# pcb.net
KiCad netlist of a schematic drawn in EAGLE
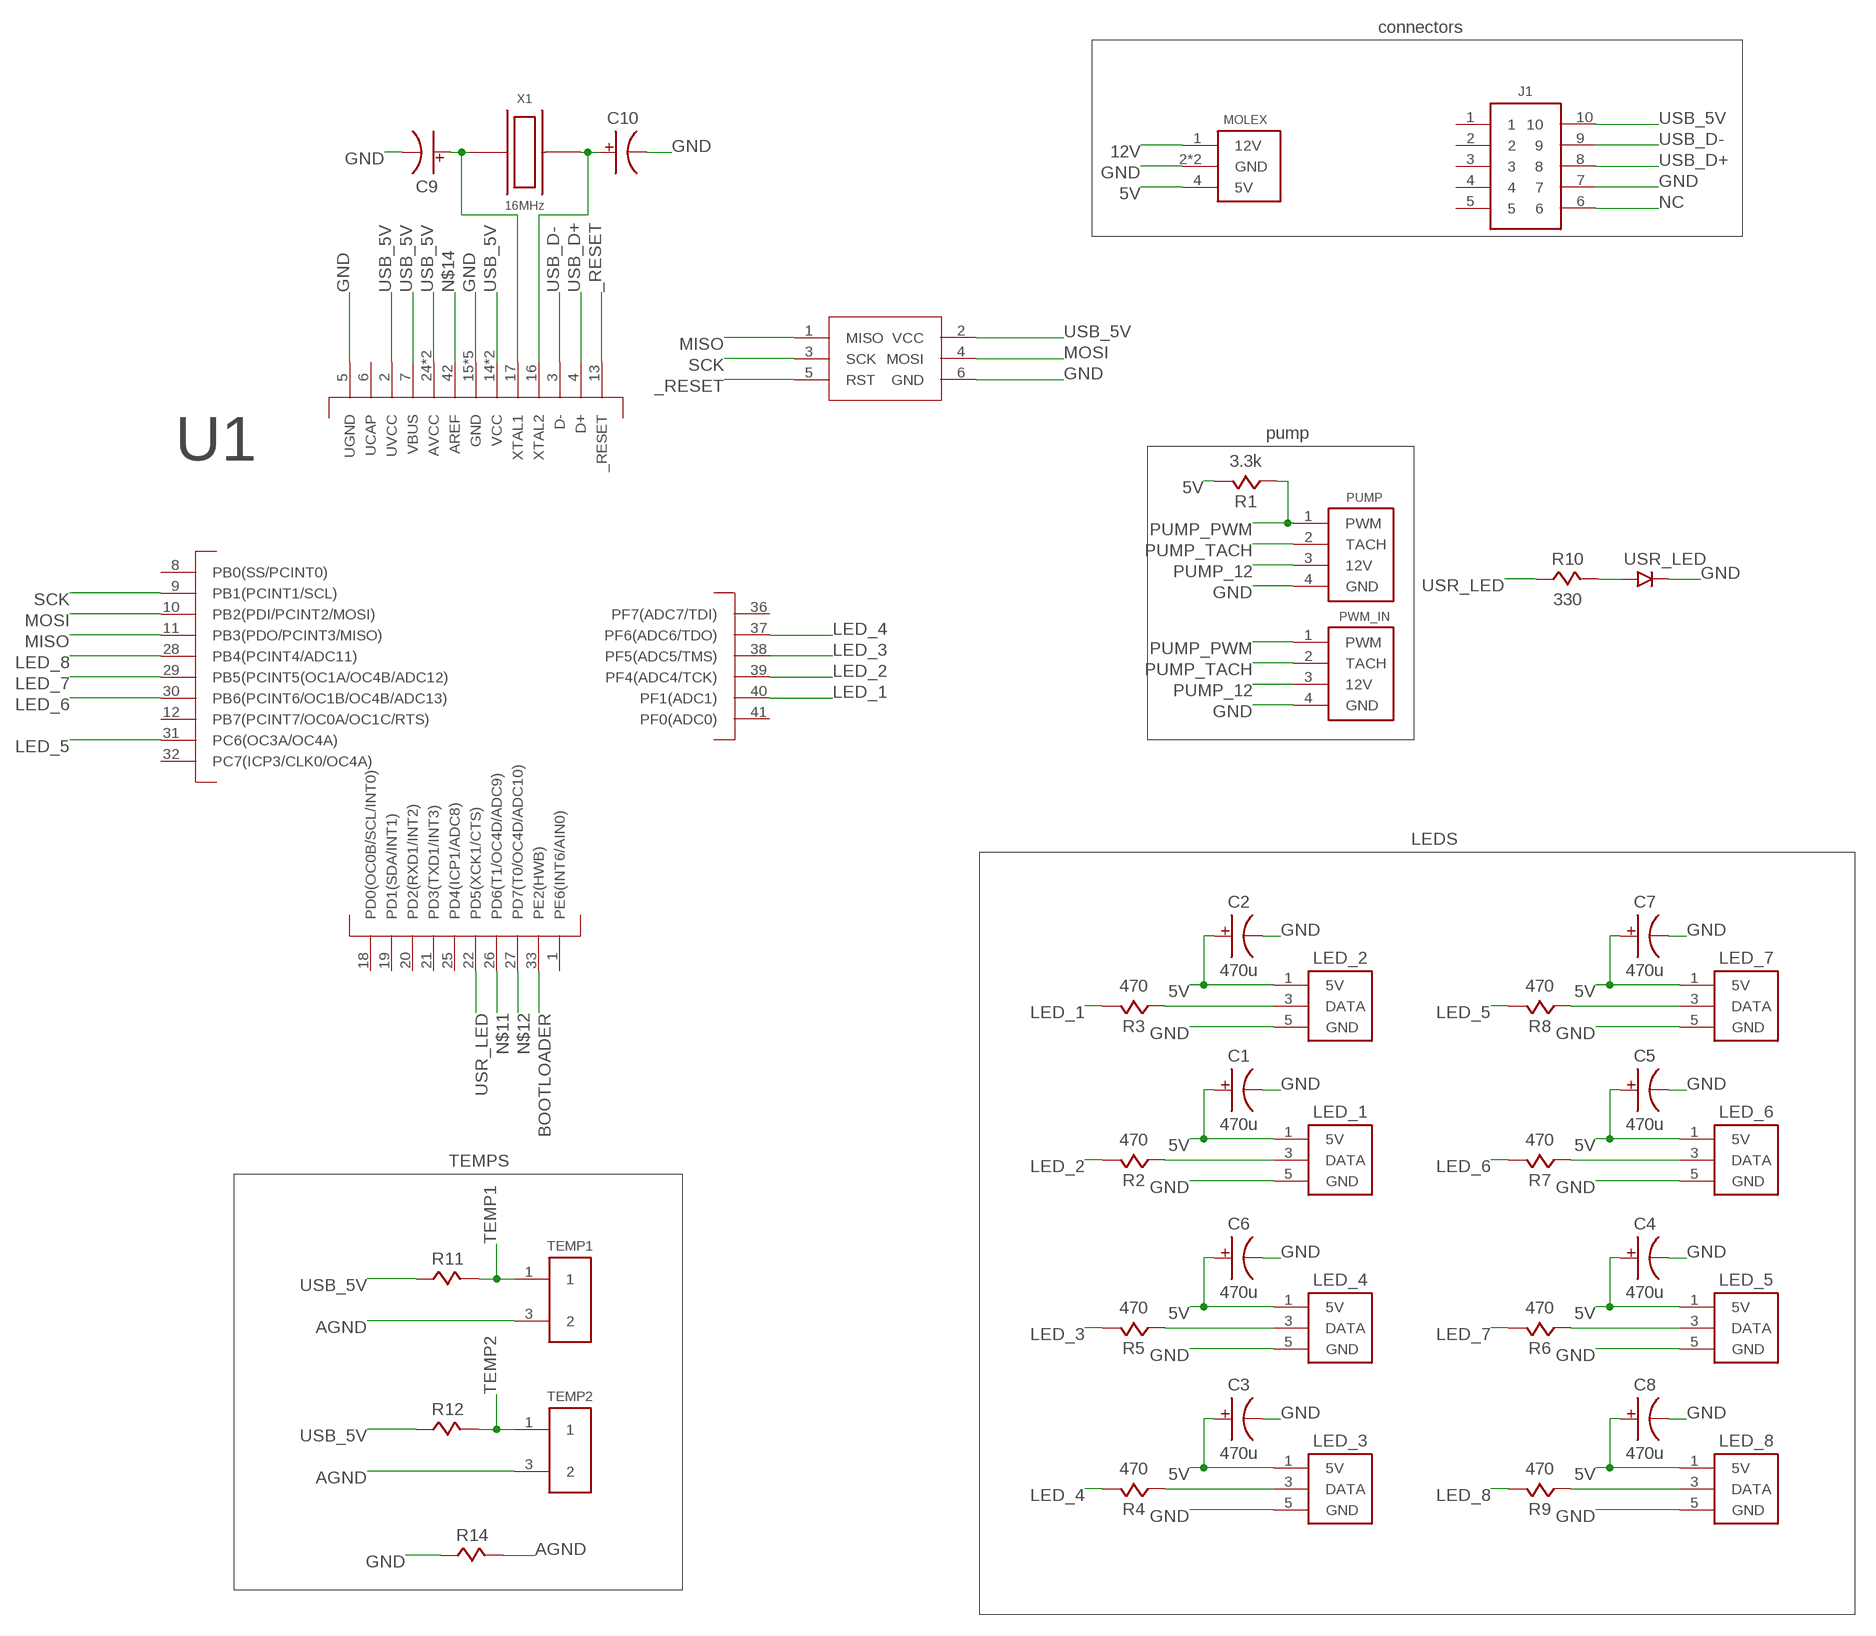
[diagram p0: schematic, sheet 1]

(export (version "E")
  (design (tool "Eeschema 10.0.6"))
  (components
    (comp (ref "C1")
      (value "470u")
      (footprint "eagle-import:0805")
      (libsource (lib "eagle-import") (part "CAPACITOR0805"))
    )
    (comp (ref "C2")
      (value "470u")
      (footprint "eagle-import:0805")
      (libsource (lib "eagle-import") (part "CAPACITOR0805"))
    )
    (comp (ref "C3")
      (value "470u")
      (footprint "eagle-import:0805")
      (libsource (lib "eagle-import") (part "CAPACITOR0805"))
    )
    (comp (ref "C4")
      (value "470u")
      (footprint "eagle-import:0805")
      (libsource (lib "eagle-import") (part "CAPACITOR0805"))
    )
    (comp (ref "C5")
      (value "470u")
      (footprint "eagle-import:0805")
      (libsource (lib "eagle-import") (part "CAPACITOR0805"))
    )
    (comp (ref "C6")
      (value "470u")
      (footprint "eagle-import:0805")
      (libsource (lib "eagle-import") (part "CAPACITOR0805"))
    )
    (comp (ref "C7")
      (value "470u")
      (footprint "eagle-import:0805")
      (libsource (lib "eagle-import") (part "CAPACITOR0805"))
    )
    (comp (ref "C8")
      (value "470u")
      (footprint "eagle-import:0805")
      (libsource (lib "eagle-import") (part "CAPACITOR0805"))
    )
    (comp (ref "C9")
      (value "CAPACITOR0805")
      (footprint "eagle-import:0805")
      (libsource (lib "eagle-import") (part "CAPACITOR0805"))
    )
    (comp (ref "C10")
      (value "CAPACITOR0805")
      (footprint "eagle-import:0805")
      (libsource (lib "eagle-import") (part "CAPACITOR0805"))
    )
    (comp (ref "J1")
      (value "FEMALE_HEADER_5X2SMT")
      (footprint "eagle-import:5X2_HEADER_SMT")
      (libsource (lib "eagle-import") (part "FEMALE_HEADER_5X2SMT"))
    )
    (comp (ref "J2")
      (value "ISP_CONN_6PIN")
      (footprint "eagle-import:3X2_HEADER_SMT")
      (libsource (lib "eagle-import") (part "ISP_CONN_6PIN"))
    )
    (comp (ref "LED_1")
      (value "WS2812B_3")
      (footprint "eagle-import:3X1_HEADER")
      (libsource (lib "eagle-import") (part "WS2812B_3"))
    )
    (comp (ref "LED_2")
      (value "WS2812B_3")
      (footprint "eagle-import:3X1_HEADER")
      (libsource (lib "eagle-import") (part "WS2812B_3"))
    )
    (comp (ref "LED_3")
      (value "WS2812B_3")
      (footprint "eagle-import:3X1_HEADER")
      (libsource (lib "eagle-import") (part "WS2812B_3"))
    )
    (comp (ref "LED_4")
      (value "WS2812B_3")
      (footprint "eagle-import:3X1_HEADER")
      (libsource (lib "eagle-import") (part "WS2812B_3"))
    )
    (comp (ref "LED_5")
      (value "WS2812B_3")
      (footprint "eagle-import:3X1_HEADER")
      (libsource (lib "eagle-import") (part "WS2812B_3"))
    )
    (comp (ref "LED_6")
      (value "WS2812B_3")
      (footprint "eagle-import:3X1_HEADER")
      (libsource (lib "eagle-import") (part "WS2812B_3"))
    )
    (comp (ref "LED_7")
      (value "WS2812B_3")
      (footprint "eagle-import:3X1_HEADER")
      (libsource (lib "eagle-import") (part "WS2812B_3"))
    )
    (comp (ref "LED_8")
      (value "WS2812B_3")
      (footprint "eagle-import:3X1_HEADER")
      (libsource (lib "eagle-import") (part "WS2812B_3"))
    )
    (comp (ref "MOLEX")
      (value "MOLEX_POWER")
      (footprint "eagle-import:MOLEX_POWER")
      (libsource (lib "eagle-import") (part "MOLEX_POWER"))
    )
    (comp (ref "PUMP")
      (value "4PIN_LED_HEADER")
      (footprint "eagle-import:4PIN_FAN_HEADER_THT")
      (libsource (lib "eagle-import") (part "4PIN_LED_HEADER"))
    )
    (comp (ref "PWM_IN")
      (value "4PIN_LED_HEADER")
      (footprint "eagle-import:4PIN_FAN_HEADER_THT")
      (libsource (lib "eagle-import") (part "4PIN_LED_HEADER"))
    )
    (comp (ref "R1")
      (value "3.3k")
      (footprint "eagle-import:0805")
      (libsource (lib "eagle-import") (part "RESISTOR"))
    )
    (comp (ref "R2")
      (value "470")
      (footprint "eagle-import:0805")
      (libsource (lib "eagle-import") (part "RESISTOR"))
    )
    (comp (ref "R3")
      (value "470")
      (footprint "eagle-import:0805")
      (libsource (lib "eagle-import") (part "RESISTOR"))
    )
    (comp (ref "R4")
      (value "470")
      (footprint "eagle-import:0805")
      (libsource (lib "eagle-import") (part "RESISTOR"))
    )
    (comp (ref "R5")
      (value "470")
      (footprint "eagle-import:0805")
      (libsource (lib "eagle-import") (part "RESISTOR"))
    )
    (comp (ref "R6")
      (value "470")
      (footprint "eagle-import:0805")
      (libsource (lib "eagle-import") (part "RESISTOR"))
    )
    (comp (ref "R7")
      (value "470")
      (footprint "eagle-import:0805")
      (libsource (lib "eagle-import") (part "RESISTOR"))
    )
    (comp (ref "R8")
      (value "470")
      (footprint "eagle-import:0805")
      (libsource (lib "eagle-import") (part "RESISTOR"))
    )
    (comp (ref "R9")
      (value "470")
      (footprint "eagle-import:0805")
      (libsource (lib "eagle-import") (part "RESISTOR"))
    )
    (comp (ref "R10")
      (value "330")
      (footprint "eagle-import:0805")
      (libsource (lib "eagle-import") (part "RESISTOR"))
    )
    (comp (ref "R11")
      (value "RESISTOR")
      (footprint "eagle-import:0805")
      (libsource (lib "eagle-import") (part "RESISTOR"))
    )
    (comp (ref "R12")
      (value "RESISTOR")
      (footprint "eagle-import:0805")
      (libsource (lib "eagle-import") (part "RESISTOR"))
    )
    (comp (ref "R14")
      (value "RESISTOR")
      (footprint "eagle-import:0805")
      (libsource (lib "eagle-import") (part "RESISTOR"))
    )
    (comp (ref "TEMP1")
      (value "FEMALE_HEADER_2X1")
      (footprint "eagle-import:2X1_HEADER")
      (libsource (lib "eagle-import") (part "FEMALE_HEADER_2X1"))
    )
    (comp (ref "TEMP2")
      (value "FEMALE_HEADER_2X1")
      (footprint "eagle-import:2X1_HEADER")
      (libsource (lib "eagle-import") (part "FEMALE_HEADER_2X1"))
    )
    (comp (ref "U1")
      (value "ATMEGA32U4")
      (footprint "eagle-import:QFN44")
      (libsource (lib "eagle-import") (part "ATMEGA32U4"))
    )
    (comp (ref "USR_LED")
      (value "LED")
      (footprint "eagle-import:0805")
      (libsource (lib "eagle-import") (part "LED"))
    )
    (comp (ref "X1")
      (value "16MHz")
      (footprint "eagle-import:3.2X2.5_OSC")
      (libsource (lib "eagle-import") (part "QUARTZ"))
    )
  )
  (nets
    (net (code "1") (name "/5V") (class "Default")
      (node (ref "C1") (pin "1") (pinfunction "P$1_1") (pintype "bidirectional"))
      (node (ref "C2") (pin "1") (pinfunction "P$1_1") (pintype "bidirectional"))
      (node (ref "C3") (pin "1") (pinfunction "P$1_1") (pintype "bidirectional"))
      (node (ref "C4") (pin "1") (pinfunction "P$1_1") (pintype "bidirectional"))
      (node (ref "C5") (pin "1") (pinfunction "P$1_1") (pintype "bidirectional"))
      (node (ref "C6") (pin "1") (pinfunction "P$1_1") (pintype "bidirectional"))
      (node (ref "C7") (pin "1") (pinfunction "P$1_1") (pintype "bidirectional"))
      (node (ref "C8") (pin "1") (pinfunction "P$1_1") (pintype "bidirectional"))
      (node (ref "LED_1") (pin "1") (pinfunction "5V_1") (pintype "bidirectional"))
      (node (ref "LED_2") (pin "1") (pinfunction "5V_1") (pintype "bidirectional"))
      (node (ref "LED_3") (pin "1") (pinfunction "5V_1") (pintype "bidirectional"))
      (node (ref "LED_4") (pin "1") (pinfunction "5V_1") (pintype "bidirectional"))
      (node (ref "LED_5") (pin "1") (pinfunction "5V_1") (pintype "bidirectional"))
      (node (ref "LED_6") (pin "1") (pinfunction "5V_1") (pintype "bidirectional"))
      (node (ref "LED_7") (pin "1") (pinfunction "5V_1") (pintype "bidirectional"))
      (node (ref "LED_8") (pin "1") (pinfunction "5V_1") (pintype "bidirectional"))
      (node (ref "MOLEX") (pin "4") (pinfunction "5V_4") (pintype "bidirectional"))
      (node (ref "R1") (pin "2") (pinfunction "2_2") (pintype "bidirectional"))
    )
    (net (code "2") (name "/12V") (class "Default")
      (node (ref "MOLEX") (pin "1") (pinfunction "12V_1") (pintype "bidirectional"))
    )
    (net (code "3") (name "/AGND") (class "Default")
      (node (ref "R14") (pin "2") (pinfunction "2_2") (pintype "bidirectional"))
      (node (ref "TEMP1") (pin "3") (pinfunction "2_3") (pintype "bidirectional"))
      (node (ref "TEMP2") (pin "3") (pinfunction "2_3") (pintype "bidirectional"))
    )
    (net (code "4") (name "/BOOTLOADER") (class "Default")
      (node (ref "U1") (pin "33") (pinfunction "PE2(HWB)_33") (pintype "bidirectional"))
    )
    (net (code "5") (name "/GND") (class "Default")
      (node (ref "C1") (pin "2") (pinfunction "P$2_2") (pintype "bidirectional"))
      (node (ref "C10") (pin "2") (pinfunction "P$2_2") (pintype "bidirectional"))
      (node (ref "C2") (pin "2") (pinfunction "P$2_2") (pintype "bidirectional"))
      (node (ref "C3") (pin "2") (pinfunction "P$2_2") (pintype "bidirectional"))
      (node (ref "C4") (pin "2") (pinfunction "P$2_2") (pintype "bidirectional"))
      (node (ref "C5") (pin "2") (pinfunction "P$2_2") (pintype "bidirectional"))
      (node (ref "C6") (pin "2") (pinfunction "P$2_2") (pintype "bidirectional"))
      (node (ref "C7") (pin "2") (pinfunction "P$2_2") (pintype "bidirectional"))
      (node (ref "C8") (pin "2") (pinfunction "P$2_2") (pintype "bidirectional"))
      (node (ref "C9") (pin "2") (pinfunction "P$2_2") (pintype "bidirectional"))
      (node (ref "J1") (pin "7") (pinfunction "7_7") (pintype "bidirectional"))
      (node (ref "J2") (pin "6") (pinfunction "GND_6") (pintype "bidirectional"))
      (node (ref "LED_1") (pin "5") (pinfunction "GND_5") (pintype "bidirectional"))
      (node (ref "LED_2") (pin "5") (pinfunction "GND_5") (pintype "bidirectional"))
      (node (ref "LED_3") (pin "5") (pinfunction "GND_5") (pintype "bidirectional"))
      (node (ref "LED_4") (pin "5") (pinfunction "GND_5") (pintype "bidirectional"))
      (node (ref "LED_5") (pin "5") (pinfunction "GND_5") (pintype "bidirectional"))
      (node (ref "LED_6") (pin "5") (pinfunction "GND_5") (pintype "bidirectional"))
      (node (ref "LED_7") (pin "5") (pinfunction "GND_5") (pintype "bidirectional"))
      (node (ref "LED_8") (pin "5") (pinfunction "GND_5") (pintype "bidirectional"))
      (node (ref "MOLEX") (pin "2") (pinfunction "GND_2") (pintype "bidirectional"))
      (node (ref "MOLEX") (pin "3") (pinfunction "GND_3") (pintype "bidirectional"))
      (node (ref "PUMP") (pin "4") (pinfunction "GND_4") (pintype "bidirectional"))
      (node (ref "PWM_IN") (pin "4") (pinfunction "GND_4") (pintype "bidirectional"))
      (node (ref "R14") (pin "1") (pinfunction "1_1") (pintype "bidirectional"))
      (node (ref "U1") (pin "15") (pinfunction "GND_15") (pintype "bidirectional"))
      (node (ref "U1") (pin "23") (pinfunction "GND_23") (pintype "bidirectional"))
      (node (ref "U1") (pin "35") (pinfunction "GND_35") (pintype "bidirectional"))
      (node (ref "U1") (pin "43") (pinfunction "GND_43") (pintype "bidirectional"))
      (node (ref "U1") (pin "45") (pinfunction "GND_45") (pintype "bidirectional"))
      (node (ref "U1") (pin "5") (pinfunction "UGND_5") (pintype "bidirectional"))
      (node (ref "USR_LED") (pin "2") (pinfunction "2_2") (pintype "bidirectional"))
    )
    (net (code "6") (name "/LED_1") (class "Default")
      (node (ref "R3") (pin "2") (pinfunction "2_2") (pintype "bidirectional"))
      (node (ref "U1") (pin "40") (pinfunction "PF1(ADC1)_40") (pintype "bidirectional"))
    )
    (net (code "7") (name "/LED_2") (class "Default")
      (node (ref "R2") (pin "2") (pinfunction "2_2") (pintype "bidirectional"))
      (node (ref "U1") (pin "39") (pinfunction "PF4(ADC4/TCK)_39") (pintype "bidirectional"))
    )
    (net (code "8") (name "/LED_3") (class "Default")
      (node (ref "R5") (pin "2") (pinfunction "2_2") (pintype "bidirectional"))
      (node (ref "U1") (pin "38") (pinfunction "PF5(ADC5/TMS)_38") (pintype "bidirectional"))
    )
    (net (code "9") (name "/LED_4") (class "Default")
      (node (ref "R4") (pin "2") (pinfunction "2_2") (pintype "bidirectional"))
      (node (ref "U1") (pin "37") (pinfunction "PF6(ADC6/TDO)_37") (pintype "bidirectional"))
    )
    (net (code "10") (name "/LED_5") (class "Default")
      (node (ref "R8") (pin "2") (pinfunction "2_2") (pintype "bidirectional"))
      (node (ref "U1") (pin "31") (pinfunction "PC6(OC3A/OC4A)_31") (pintype "bidirectional"))
    )
    (net (code "11") (name "/LED_6") (class "Default")
      (node (ref "R7") (pin "2") (pinfunction "2_2") (pintype "bidirectional"))
      (node (ref "U1") (pin "30") (pinfunction "PB6(PCINT6/OC1B/OC4B/ADC13)_30") (pintype "bidirectional"))
    )
    (net (code "12") (name "/LED_7") (class "Default")
      (node (ref "R6") (pin "2") (pinfunction "2_2") (pintype "bidirectional"))
      (node (ref "U1") (pin "29") (pinfunction "PB5(PCINT5(OC1A/OC4B/ADC12)_29") (pintype "bidirectional"))
    )
    (net (code "13") (name "/LED_8") (class "Default")
      (node (ref "R9") (pin "2") (pinfunction "2_2") (pintype "bidirectional"))
      (node (ref "U1") (pin "28") (pinfunction "PB4(PCINT4/ADC11)_28") (pintype "bidirectional"))
    )
    (net (code "14") (name "/MISO") (class "Default")
      (node (ref "J2") (pin "1") (pinfunction "MISO_1") (pintype "bidirectional"))
      (node (ref "U1") (pin "11") (pinfunction "PB3(PDO/PCINT3/MISO)_11") (pintype "bidirectional"))
    )
    (net (code "15") (name "/MOSI") (class "Default")
      (node (ref "J2") (pin "4") (pinfunction "MOSI_4") (pintype "bidirectional"))
      (node (ref "U1") (pin "10") (pinfunction "PB2(PDI/PCINT2/MOSI)_10") (pintype "bidirectional"))
    )
    (net (code "16") (name "/N$11") (class "Default")
      (node (ref "U1") (pin "26") (pinfunction "PD6(T1/OC4D/ADC9)_26") (pintype "bidirectional"))
    )
    (net (code "17") (name "/N$12") (class "Default")
      (node (ref "U1") (pin "27") (pinfunction "PD7(T0/OC4D/ADC10)_27") (pintype "bidirectional"))
    )
    (net (code "18") (name "/N$14") (class "Default")
      (node (ref "U1") (pin "42") (pinfunction "AREF_42") (pintype "bidirectional"))
    )
    (net (code "19") (name "/NC") (class "Default")
      (node (ref "J1") (pin "6") (pinfunction "6_6") (pintype "bidirectional"))
    )
    (net (code "20") (name "/PUMP_12") (class "Default")
      (node (ref "PUMP") (pin "3") (pinfunction "12V_3") (pintype "bidirectional"))
      (node (ref "PWM_IN") (pin "3") (pinfunction "12V_3") (pintype "bidirectional"))
    )
    (net (code "21") (name "/PUMP_PWM") (class "Default")
      (node (ref "PUMP") (pin "1") (pinfunction "PWM_1") (pintype "bidirectional"))
      (node (ref "PWM_IN") (pin "1") (pinfunction "PWM_1") (pintype "bidirectional"))
      (node (ref "R1") (pin "1") (pinfunction "1_1") (pintype "bidirectional"))
    )
    (net (code "22") (name "/PUMP_TACH") (class "Default")
      (node (ref "PUMP") (pin "2") (pinfunction "TACH_2") (pintype "bidirectional"))
      (node (ref "PWM_IN") (pin "2") (pinfunction "TACH_2") (pintype "bidirectional"))
    )
    (net (code "23") (name "/SCK") (class "Default")
      (node (ref "J2") (pin "3") (pinfunction "SCK_3") (pintype "bidirectional"))
      (node (ref "U1") (pin "9") (pinfunction "PB1(PCINT1/SCL)_9") (pintype "bidirectional"))
    )
    (net (code "24") (name "/TEMP1") (class "Default")
      (node (ref "R11") (pin "2") (pinfunction "2_2") (pintype "bidirectional"))
      (node (ref "TEMP1") (pin "1") (pinfunction "1_1") (pintype "bidirectional"))
    )
    (net (code "25") (name "/TEMP2") (class "Default")
      (node (ref "R12") (pin "2") (pinfunction "2_2") (pintype "bidirectional"))
      (node (ref "TEMP2") (pin "1") (pinfunction "1_1") (pintype "bidirectional"))
    )
    (net (code "26") (name "/USB_5V") (class "Default")
      (node (ref "J1") (pin "10") (pinfunction "10_10") (pintype "bidirectional"))
      (node (ref "J2") (pin "2") (pinfunction "VCC_2") (pintype "bidirectional"))
      (node (ref "R11") (pin "1") (pinfunction "1_1") (pintype "bidirectional"))
      (node (ref "R12") (pin "1") (pinfunction "1_1") (pintype "bidirectional"))
      (node (ref "U1") (pin "14") (pinfunction "VCC_14") (pintype "bidirectional"))
      (node (ref "U1") (pin "2") (pinfunction "UVCC_2") (pintype "bidirectional"))
      (node (ref "U1") (pin "24") (pinfunction "AVCC_24") (pintype "bidirectional"))
      (node (ref "U1") (pin "34") (pinfunction "VCC_34") (pintype "bidirectional"))
      (node (ref "U1") (pin "44") (pinfunction "AVCC_44") (pintype "bidirectional"))
      (node (ref "U1") (pin "7") (pinfunction "VBUS_7") (pintype "bidirectional"))
    )
    (net (code "27") (name "/USB_D+") (class "Default")
      (node (ref "J1") (pin "8") (pinfunction "8_8") (pintype "bidirectional"))
      (node (ref "U1") (pin "4") (pinfunction "D+_4") (pintype "bidirectional"))
    )
    (net (code "28") (name "/USB_D-") (class "Default")
      (node (ref "J1") (pin "9") (pinfunction "9_9") (pintype "bidirectional"))
      (node (ref "U1") (pin "3") (pinfunction "D-_3") (pintype "bidirectional"))
    )
    (net (code "29") (name "/USR_LED") (class "Default")
      (node (ref "R10") (pin "1") (pinfunction "1_1") (pintype "bidirectional"))
      (node (ref "U1") (pin "22") (pinfunction "PD5(XCK1/CTS)_22") (pintype "bidirectional"))
    )
    (net (code "30") (name "/_RESET") (class "Default")
      (node (ref "J2") (pin "5") (pinfunction "RST_5") (pintype "bidirectional"))
      (node (ref "U1") (pin "13") (pinfunction "_RESET_13") (pintype "bidirectional"))
    )
    (net (code "31") (name "Net-(C9-P$1)") (class "Default")
      (node (ref "C9") (pin "1") (pinfunction "P$1_1") (pintype "bidirectional"))
      (node (ref "U1") (pin "17") (pinfunction "XTAL1_17") (pintype "bidirectional"))
      (node (ref "X1") (pin "1") (pinfunction "P$1_1") (pintype "bidirectional"))
    )
    (net (code "32") (name "Net-(C10-P$1)") (class "Default")
      (node (ref "C10") (pin "1") (pinfunction "P$1_1") (pintype "bidirectional"))
      (node (ref "U1") (pin "16") (pinfunction "XTAL2_16") (pintype "bidirectional"))
      (node (ref "X1") (pin "3") (pinfunction "P$2_3") (pintype "bidirectional"))
    )
    (net (code "33") (name "Net-(LED_1-DATA)") (class "Default")
      (node (ref "LED_1") (pin "3") (pinfunction "DATA_3") (pintype "bidirectional"))
      (node (ref "R2") (pin "1") (pinfunction "1_1") (pintype "bidirectional"))
    )
    (net (code "34") (name "Net-(LED_2-DATA)") (class "Default")
      (node (ref "LED_2") (pin "3") (pinfunction "DATA_3") (pintype "bidirectional"))
      (node (ref "R3") (pin "1") (pinfunction "1_1") (pintype "bidirectional"))
    )
    (net (code "35") (name "Net-(LED_3-DATA)") (class "Default")
      (node (ref "LED_3") (pin "3") (pinfunction "DATA_3") (pintype "bidirectional"))
      (node (ref "R4") (pin "1") (pinfunction "1_1") (pintype "bidirectional"))
    )
    (net (code "36") (name "Net-(LED_4-DATA)") (class "Default")
      (node (ref "LED_4") (pin "3") (pinfunction "DATA_3") (pintype "bidirectional"))
      (node (ref "R5") (pin "1") (pinfunction "1_1") (pintype "bidirectional"))
    )
    (net (code "37") (name "Net-(LED_5-DATA)") (class "Default")
      (node (ref "LED_5") (pin "3") (pinfunction "DATA_3") (pintype "bidirectional"))
      (node (ref "R6") (pin "1") (pinfunction "1_1") (pintype "bidirectional"))
    )
    (net (code "38") (name "Net-(LED_6-DATA)") (class "Default")
      (node (ref "LED_6") (pin "3") (pinfunction "DATA_3") (pintype "bidirectional"))
      (node (ref "R7") (pin "1") (pinfunction "1_1") (pintype "bidirectional"))
    )
    (net (code "39") (name "Net-(LED_7-DATA)") (class "Default")
      (node (ref "LED_7") (pin "3") (pinfunction "DATA_3") (pintype "bidirectional"))
      (node (ref "R8") (pin "1") (pinfunction "1_1") (pintype "bidirectional"))
    )
    (net (code "40") (name "Net-(LED_8-DATA)") (class "Default")
      (node (ref "LED_8") (pin "3") (pinfunction "DATA_3") (pintype "bidirectional"))
      (node (ref "R9") (pin "1") (pinfunction "1_1") (pintype "bidirectional"))
    )
    (net (code "41") (name "Net-(R10-Pad2)") (class "Default")
      (node (ref "R10") (pin "2") (pinfunction "2_2") (pintype "bidirectional"))
      (node (ref "USR_LED") (pin "1") (pinfunction "1_1") (pintype "bidirectional"))
    )
    (net (code "42") (name "unconnected-(J1-Pad1)") (class "Default")
      (node (ref "J1") (pin "1") (pinfunction "1_1") (pintype "bidirectional"))
    )
    (net (code "43") (name "unconnected-(J1-Pad2)") (class "Default")
      (node (ref "J1") (pin "2") (pinfunction "2_2") (pintype "bidirectional"))
    )
    (net (code "44") (name "unconnected-(J1-Pad3)") (class "Default")
      (node (ref "J1") (pin "3") (pinfunction "3_3") (pintype "bidirectional"))
    )
    (net (code "45") (name "unconnected-(J1-Pad4)") (class "Default")
      (node (ref "J1") (pin "4") (pinfunction "4_4") (pintype "bidirectional"))
    )
    (net (code "46") (name "unconnected-(J1-Pad5)") (class "Default")
      (node (ref "J1") (pin "5") (pinfunction "5_5") (pintype "bidirectional"))
    )
    (net (code "47") (name "unconnected-(U1-PB0(SS{slash}PCINT0)-Pad8)") (class "Default")
      (node (ref "U1") (pin "8") (pinfunction "PB0(SS/PCINT0)_8") (pintype "bidirectional"))
    )
    (net (code "48") (name "unconnected-(U1-PB7(PCINT7{slash}OC0A{slash}OC1C{slash}RTS)-Pad12)") (class "Default")
      (node (ref "U1") (pin "12") (pinfunction "PB7(PCINT7/OC0A/OC1C/RTS)_12") (pintype "bidirectional"))
    )
    (net (code "49") (name "unconnected-(U1-PC7(ICP3{slash}CLK0{slash}OC4A)-Pad32)") (class "Default")
      (node (ref "U1") (pin "32") (pinfunction "PC7(ICP3/CLK0/OC4A)_32") (pintype "bidirectional"))
    )
    (net (code "50") (name "unconnected-(U1-PD0(OC0B{slash}SCL{slash}INT0)-Pad18)") (class "Default")
      (node (ref "U1") (pin "18") (pinfunction "PD0(OC0B/SCL/INT0)_18") (pintype "bidirectional"))
    )
    (net (code "51") (name "unconnected-(U1-PD1(SDA{slash}INT1)-Pad19)") (class "Default")
      (node (ref "U1") (pin "19") (pinfunction "PD1(SDA/INT1)_19") (pintype "bidirectional"))
    )
    (net (code "52") (name "unconnected-(U1-PD2(RXD1{slash}INT2)-Pad20)") (class "Default")
      (node (ref "U1") (pin "20") (pinfunction "PD2(RXD1/INT2)_20") (pintype "bidirectional"))
    )
    (net (code "53") (name "unconnected-(U1-PD3(TXD1{slash}INT3)-Pad21)") (class "Default")
      (node (ref "U1") (pin "21") (pinfunction "PD3(TXD1/INT3)_21") (pintype "bidirectional"))
    )
    (net (code "54") (name "unconnected-(U1-PD4(ICP1{slash}ADC8)-Pad25)") (class "Default")
      (node (ref "U1") (pin "25") (pinfunction "PD4(ICP1/ADC8)_25") (pintype "bidirectional"))
    )
    (net (code "55") (name "unconnected-(U1-PE6(INT6{slash}AIN0)-Pad1)") (class "Default")
      (node (ref "U1") (pin "1") (pinfunction "PE6(INT6/AIN0)_1") (pintype "bidirectional"))
    )
    (net (code "56") (name "unconnected-(U1-PF0(ADC0)-Pad41)") (class "Default")
      (node (ref "U1") (pin "41") (pinfunction "PF0(ADC0)_41") (pintype "bidirectional"))
    )
    (net (code "57") (name "unconnected-(U1-PF7(ADC7{slash}TDI)-Pad36)") (class "Default")
      (node (ref "U1") (pin "36") (pinfunction "PF7(ADC7/TDI)_36") (pintype "bidirectional"))
    )
    (net (code "58") (name "unconnected-(U1-UCAP-Pad6)") (class "Default")
      (node (ref "U1") (pin "6") (pinfunction "UCAP_6") (pintype "bidirectional"))
    )
  )
)
